# rpi_breakout.net
KiCad netlist of a schematic drawn in EAGLE
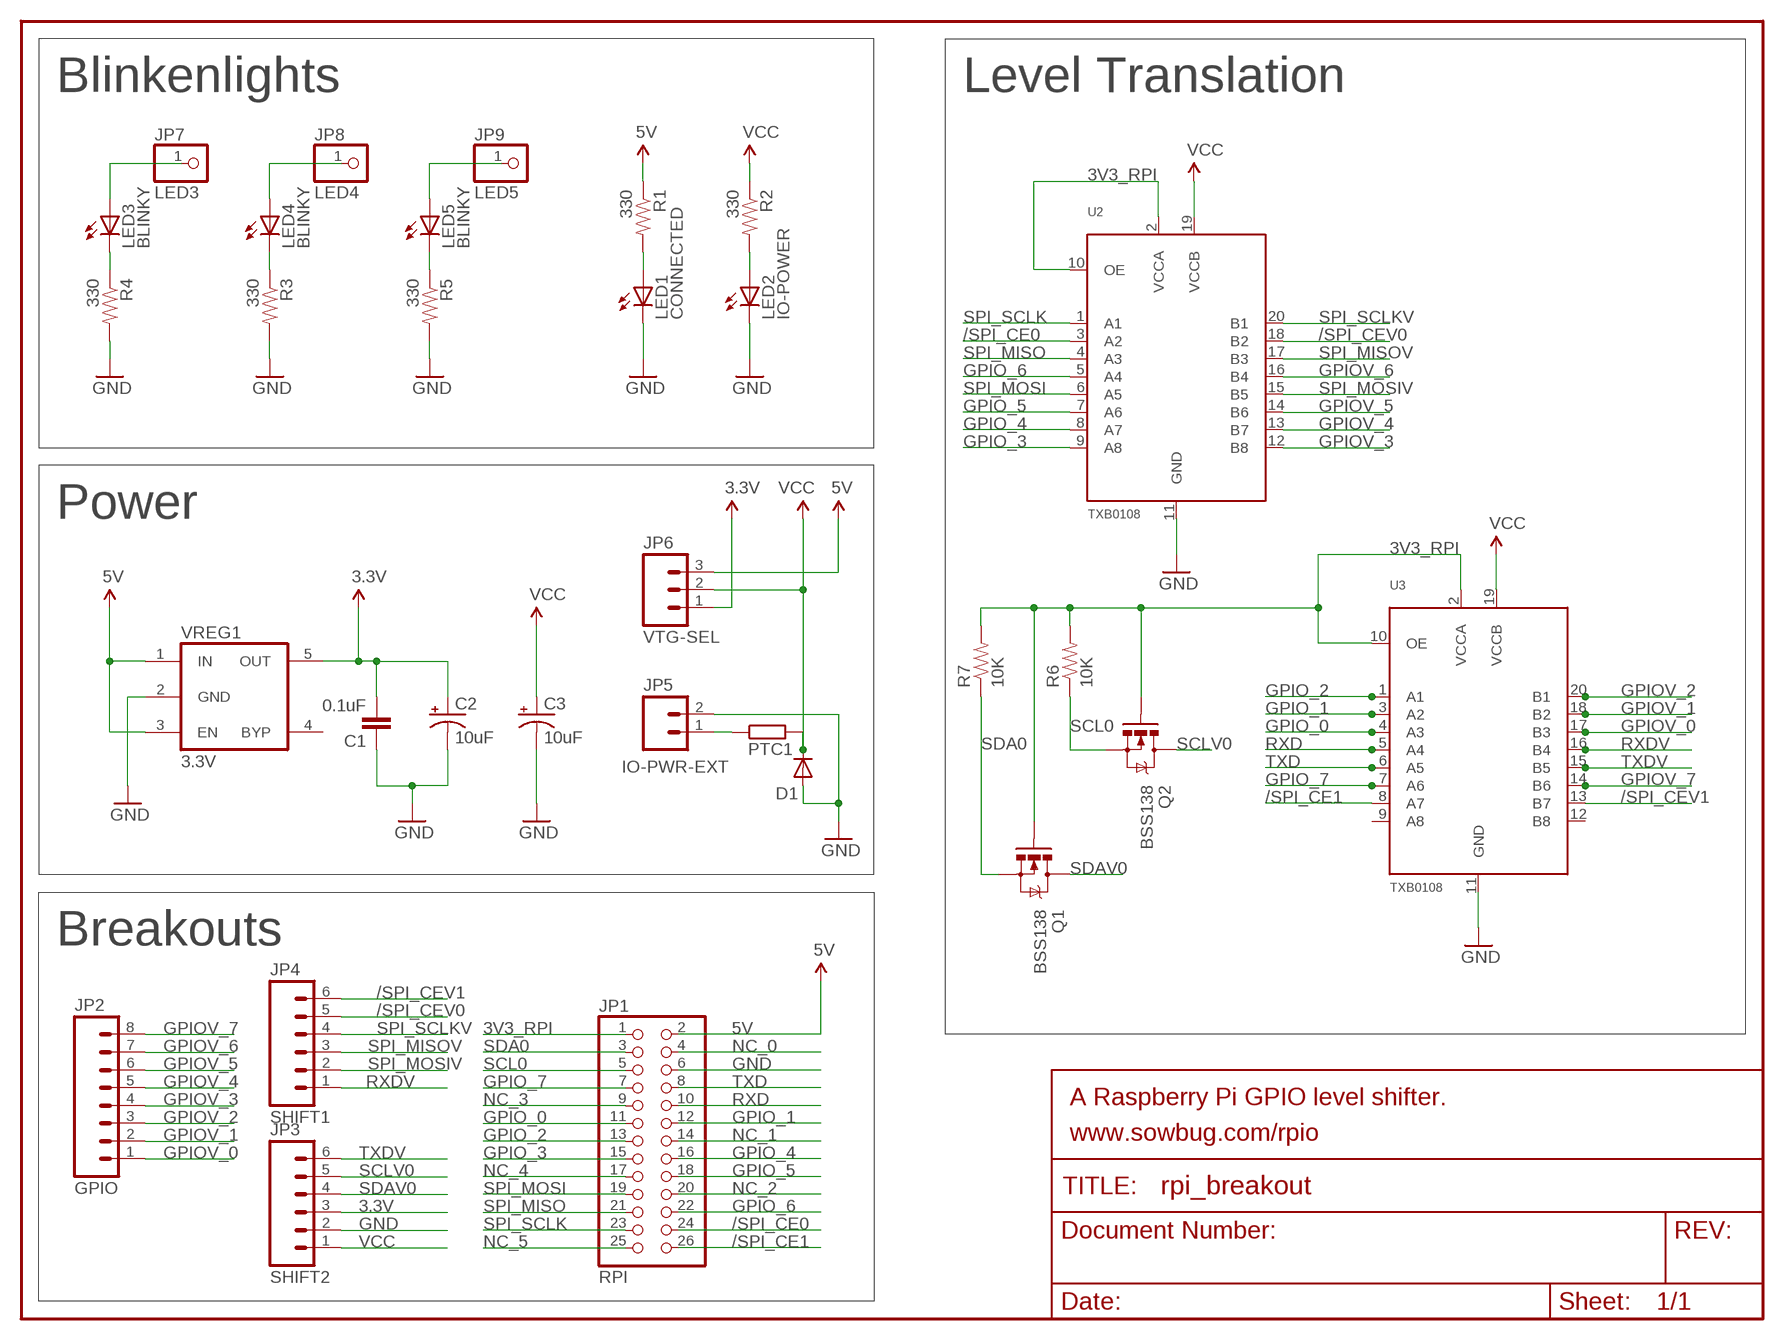
[diagram p0: schematic, sheet 1]

(export (version "E")
  (design (tool "Eeschema 10.0.6"))
  (components
    (comp (ref "C1")
      (value "0.1uF")
      (footprint "eagle-import:SPARKFUN_0805")
      (libsource (lib "eagle-import") (part "SPARKFUN_CAP0805"))
    )
    (comp (ref "C2")
      (value "10uF")
      (footprint "eagle-import:SPARKFUN_EIA3216")
      (libsource (lib "eagle-import") (part "SPARKFUN_CAP_POL1206"))
    )
    (comp (ref "C3")
      (value "10uF")
      (footprint "eagle-import:SPARKFUN_EIA3216")
      (libsource (lib "eagle-import") (part "SPARKFUN_CAP_POL1206"))
    )
    (comp (ref "D1")
      (value "SPARKFUN-DISCRETESEMI_DIODESOD")
      (footprint "eagle-import:SPARKFUN-DISCRETESEMI_SOD-323")
      (libsource (lib "eagle-import") (part "SPARKFUN-DISCRETESEMI_DIODESOD"))
    )
    (comp (ref "JP1")
      (value "RPI")
      (footprint "eagle-import:PINHEAD_2X13")
      (libsource (lib "eagle-import") (part "PINHEAD_PINHD-2X13"))
    )
    (comp (ref "JP2")
      (value "GPIO")
      (footprint "eagle-import:SPARKFUN_1X08_LOCK")
      (libsource (lib "eagle-import") (part "SPARKFUN_M08LOCK"))
    )
    (comp (ref "JP3")
      (value "SHIFT2")
      (footprint "eagle-import:SPARKFUN_1X06_LOCK")
      (libsource (lib "eagle-import") (part "SPARKFUN_M06LOCK"))
    )
    (comp (ref "JP4")
      (value "SHIFT1")
      (footprint "eagle-import:SPARKFUN_1X06_LOCK")
      (libsource (lib "eagle-import") (part "SPARKFUN_M06LOCK"))
    )
    (comp (ref "JP5")
      (value "IO-PWR-EXT")
      (footprint "eagle-import:SPARKFUN_1X02_LOCK")
      (libsource (lib "eagle-import") (part "SPARKFUN_M02LOCK"))
    )
    (comp (ref "JP6")
      (value "VTG-SEL")
      (footprint "eagle-import:SPARKFUN_1X03_LOCK")
      (libsource (lib "eagle-import") (part "SPARKFUN_M03LOCK"))
    )
    (comp (ref "JP7")
      (value "LED3")
      (footprint "eagle-import:ADAFRUIT_1X01")
      (libsource (lib "eagle-import") (part "ADAFRUIT_PINHD-1X1"))
    )
    (comp (ref "JP8")
      (value "LED4")
      (footprint "eagle-import:ADAFRUIT_1X01")
      (libsource (lib "eagle-import") (part "ADAFRUIT_PINHD-1X1"))
    )
    (comp (ref "JP9")
      (value "LED5")
      (footprint "eagle-import:ADAFRUIT_1X01")
      (libsource (lib "eagle-import") (part "ADAFRUIT_PINHD-1X1"))
    )
    (comp (ref "LED1")
      (value "CONNECTED")
      (footprint "eagle-import:PROGRAMMER_CHIP-LED0805")
      (libsource (lib "eagle-import") (part "PROGRAMMER_SPARKFUN_LED"))
    )
    (comp (ref "LED2")
      (value "IO-POWER")
      (footprint "eagle-import:PROGRAMMER_CHIP-LED0805")
      (libsource (lib "eagle-import") (part "PROGRAMMER_SPARKFUN_LED"))
    )
    (comp (ref "LED3")
      (value "BLINKY")
      (footprint "eagle-import:PROGRAMMER_CHIP-LED0805")
      (libsource (lib "eagle-import") (part "PROGRAMMER_SPARKFUN_LED"))
    )
    (comp (ref "LED4")
      (value "BLINKY")
      (footprint "eagle-import:PROGRAMMER_CHIP-LED0805")
      (libsource (lib "eagle-import") (part "PROGRAMMER_SPARKFUN_LED"))
    )
    (comp (ref "LED5")
      (value "BLINKY")
      (footprint "eagle-import:PROGRAMMER_CHIP-LED0805")
      (libsource (lib "eagle-import") (part "PROGRAMMER_SPARKFUN_LED"))
    )
    (comp (ref "PTC1")
      (value "RCL_R-EU_R1206")
      (footprint "eagle-import:RCL_R1206")
      (libsource (lib "eagle-import") (part "RCL_R-EU_R1206"))
    )
    (comp (ref "Q1")
      (value "BSS138")
      (footprint "eagle-import:SPARKFUN_SOT23-3")
      (libsource (lib "eagle-import") (part "SPARKFUN_MOSFET-NCHANNELSMD"))
    )
    (comp (ref "Q2")
      (value "BSS138")
      (footprint "eagle-import:SPARKFUN_SOT23-3")
      (libsource (lib "eagle-import") (part "SPARKFUN_MOSFET-NCHANNELSMD"))
    )
    (comp (ref "R1")
      (value "330")
      (footprint "eagle-import:SPARKFUN_0805")
      (libsource (lib "eagle-import") (part "SPARKFUN_RESISTOR0805-RES"))
    )
    (comp (ref "R2")
      (value "330")
      (footprint "eagle-import:SPARKFUN_0805")
      (libsource (lib "eagle-import") (part "SPARKFUN_RESISTOR0805-RES"))
    )
    (comp (ref "R3")
      (value "330")
      (footprint "eagle-import:SPARKFUN_0805")
      (libsource (lib "eagle-import") (part "SPARKFUN_RESISTOR0805-RES"))
    )
    (comp (ref "R4")
      (value "330")
      (footprint "eagle-import:SPARKFUN_0805")
      (libsource (lib "eagle-import") (part "SPARKFUN_RESISTOR0805-RES"))
    )
    (comp (ref "R5")
      (value "330")
      (footprint "eagle-import:SPARKFUN_0805")
      (libsource (lib "eagle-import") (part "SPARKFUN_RESISTOR0805-RES"))
    )
    (comp (ref "R6")
      (value "10K")
      (footprint "eagle-import:SPARKFUN_0805")
      (libsource (lib "eagle-import") (part "SPARKFUN_RESISTOR0805-RES"))
    )
    (comp (ref "R7")
      (value "10K")
      (footprint "eagle-import:SPARKFUN_0805")
      (libsource (lib "eagle-import") (part "SPARKFUN_RESISTOR0805-RES"))
    )
    (comp (ref "U2")
      (value "TXB0108")
      (footprint "eagle-import:RPI_BREAKOUT_TSSOP20")
      (libsource (lib "eagle-import") (part "RPI_BREAKOUT_TXB0108PWR"))
    )
    (comp (ref "U3")
      (value "TXB0108")
      (footprint "eagle-import:RPI_BREAKOUT_TSSOP20")
      (libsource (lib "eagle-import") (part "RPI_BREAKOUT_TXB0108PWR"))
    )
    (comp (ref "VREG1")
      (value "3.3V")
      (footprint "eagle-import:DP_DEVICES_SOT-23-5")
      (libsource (lib "eagle-import") (part "DP_DEVICES_IC_VREG_5PINS-SOT-23-5"))
    )
  )
  (nets
    (net (code "1") (name "/3V3_RPI") (class "Default")
      (node (ref "JP1") (pin "1") (pinfunction "1_1") (pintype "passive"))
      (node (ref "Q1") (pin "1") (pinfunction "G_1") (pintype "passive"))
      (node (ref "Q2") (pin "1") (pinfunction "G_1") (pintype "passive"))
      (node (ref "R6") (pin "2") (pinfunction "2_2") (pintype "passive"))
      (node (ref "R7") (pin "2") (pinfunction "2_2") (pintype "passive"))
      (node (ref "U2") (pin "10") (pinfunction "OE_10") (pintype "bidirectional"))
      (node (ref "U2") (pin "2") (pinfunction "VCCA_2") (pintype "bidirectional"))
      (node (ref "U3") (pin "10") (pinfunction "OE_10") (pintype "bidirectional"))
      (node (ref "U3") (pin "2") (pinfunction "VCCA_2") (pintype "bidirectional"))
    )
    (net (code "2") (name "/GPIOV_0") (class "Default")
      (node (ref "JP2") (pin "1") (pinfunction "1_1") (pintype "passive"))
      (node (ref "U3") (pin "17") (pinfunction "B3_17") (pintype "bidirectional"))
    )
    (net (code "3") (name "/GPIOV_1") (class "Default")
      (node (ref "JP2") (pin "2") (pinfunction "2_2") (pintype "passive"))
      (node (ref "U3") (pin "18") (pinfunction "B2_18") (pintype "bidirectional"))
    )
    (net (code "4") (name "/GPIOV_2") (class "Default")
      (node (ref "JP2") (pin "3") (pinfunction "3_3") (pintype "passive"))
      (node (ref "U3") (pin "20") (pinfunction "B1_20") (pintype "bidirectional"))
    )
    (net (code "5") (name "/GPIOV_3") (class "Default")
      (node (ref "JP2") (pin "4") (pinfunction "4_4") (pintype "passive"))
      (node (ref "U2") (pin "12") (pinfunction "B8_12") (pintype "bidirectional"))
    )
    (net (code "6") (name "/GPIOV_4") (class "Default")
      (node (ref "JP2") (pin "5") (pinfunction "5_5") (pintype "passive"))
      (node (ref "U2") (pin "13") (pinfunction "B7_13") (pintype "bidirectional"))
    )
    (net (code "7") (name "/GPIOV_5") (class "Default")
      (node (ref "JP2") (pin "6") (pinfunction "6_6") (pintype "passive"))
      (node (ref "U2") (pin "14") (pinfunction "B6_14") (pintype "bidirectional"))
    )
    (net (code "8") (name "/GPIOV_6") (class "Default")
      (node (ref "JP2") (pin "7") (pinfunction "7_7") (pintype "passive"))
      (node (ref "U2") (pin "16") (pinfunction "B4_16") (pintype "bidirectional"))
    )
    (net (code "9") (name "/GPIOV_7") (class "Default")
      (node (ref "JP2") (pin "8") (pinfunction "8_8") (pintype "passive"))
      (node (ref "U3") (pin "14") (pinfunction "B6_14") (pintype "bidirectional"))
    )
    (net (code "10") (name "/GPIO_0") (class "Default")
      (node (ref "JP1") (pin "11") (pinfunction "11_11") (pintype "passive"))
      (node (ref "U3") (pin "4") (pinfunction "A3_4") (pintype "bidirectional"))
    )
    (net (code "11") (name "/GPIO_1") (class "Default")
      (node (ref "JP1") (pin "12") (pinfunction "12_12") (pintype "passive"))
      (node (ref "U3") (pin "3") (pinfunction "A2_3") (pintype "bidirectional"))
    )
    (net (code "12") (name "/GPIO_2") (class "Default")
      (node (ref "JP1") (pin "13") (pinfunction "13_13") (pintype "passive"))
      (node (ref "U3") (pin "1") (pinfunction "A1_1") (pintype "bidirectional"))
    )
    (net (code "13") (name "/GPIO_3") (class "Default")
      (node (ref "JP1") (pin "15") (pinfunction "15_15") (pintype "passive"))
      (node (ref "U2") (pin "9") (pinfunction "A8_9") (pintype "bidirectional"))
    )
    (net (code "14") (name "/GPIO_4") (class "Default")
      (node (ref "JP1") (pin "16") (pinfunction "16_16") (pintype "passive"))
      (node (ref "U2") (pin "8") (pinfunction "A7_8") (pintype "bidirectional"))
    )
    (net (code "15") (name "/GPIO_5") (class "Default")
      (node (ref "JP1") (pin "18") (pinfunction "18_18") (pintype "passive"))
      (node (ref "U2") (pin "7") (pinfunction "A6_7") (pintype "bidirectional"))
    )
    (net (code "16") (name "/GPIO_6") (class "Default")
      (node (ref "JP1") (pin "22") (pinfunction "22_22") (pintype "passive"))
      (node (ref "U2") (pin "5") (pinfunction "A4_5") (pintype "bidirectional"))
    )
    (net (code "17") (name "/GPIO_7") (class "Default")
      (node (ref "JP1") (pin "7") (pinfunction "7_7") (pintype "passive"))
      (node (ref "U3") (pin "7") (pinfunction "A6_7") (pintype "bidirectional"))
    )
    (net (code "18") (name "/NC_0") (class "Default")
      (node (ref "JP1") (pin "4") (pinfunction "4_4") (pintype "passive"))
    )
    (net (code "19") (name "/NC_1") (class "Default")
      (node (ref "JP1") (pin "14") (pinfunction "14_14") (pintype "passive"))
    )
    (net (code "20") (name "/NC_2") (class "Default")
      (node (ref "JP1") (pin "20") (pinfunction "20_20") (pintype "passive"))
    )
    (net (code "21") (name "/NC_3") (class "Default")
      (node (ref "JP1") (pin "9") (pinfunction "9_9") (pintype "passive"))
    )
    (net (code "22") (name "/NC_4") (class "Default")
      (node (ref "JP1") (pin "17") (pinfunction "17_17") (pintype "passive"))
    )
    (net (code "23") (name "/NC_5") (class "Default")
      (node (ref "JP1") (pin "25") (pinfunction "25_25") (pintype "passive"))
    )
    (net (code "24") (name "/RXD") (class "Default")
      (node (ref "JP1") (pin "10") (pinfunction "10_10") (pintype "passive"))
      (node (ref "U3") (pin "5") (pinfunction "A4_5") (pintype "bidirectional"))
    )
    (net (code "25") (name "/RXDV") (class "Default")
      (node (ref "JP4") (pin "1") (pinfunction "1_1") (pintype "passive"))
      (node (ref "U3") (pin "16") (pinfunction "B4_16") (pintype "bidirectional"))
    )
    (net (code "26") (name "/SCL0") (class "Default")
      (node (ref "JP1") (pin "5") (pinfunction "5_5") (pintype "passive"))
      (node (ref "Q2") (pin "2") (pinfunction "S_2") (pintype "passive"))
      (node (ref "R6") (pin "1") (pinfunction "1_1") (pintype "passive"))
    )
    (net (code "27") (name "/SCLV0") (class "Default")
      (node (ref "JP3") (pin "5") (pinfunction "5_5") (pintype "passive"))
      (node (ref "Q2") (pin "3") (pinfunction "D_3") (pintype "passive"))
    )
    (net (code "28") (name "/SDA0") (class "Default")
      (node (ref "JP1") (pin "3") (pinfunction "3_3") (pintype "passive"))
      (node (ref "Q1") (pin "2") (pinfunction "S_2") (pintype "passive"))
      (node (ref "R7") (pin "1") (pinfunction "1_1") (pintype "passive"))
    )
    (net (code "29") (name "/SDAV0") (class "Default")
      (node (ref "JP3") (pin "4") (pinfunction "4_4") (pintype "passive"))
      (node (ref "Q1") (pin "3") (pinfunction "D_3") (pintype "passive"))
    )
    (net (code "30") (name "/SPI_MISO") (class "Default")
      (node (ref "JP1") (pin "21") (pinfunction "21_21") (pintype "passive"))
      (node (ref "U2") (pin "4") (pinfunction "A3_4") (pintype "bidirectional"))
    )
    (net (code "31") (name "/SPI_MISOV") (class "Default")
      (node (ref "JP4") (pin "3") (pinfunction "3_3") (pintype "passive"))
      (node (ref "U2") (pin "17") (pinfunction "B3_17") (pintype "bidirectional"))
    )
    (net (code "32") (name "/SPI_MOSI") (class "Default")
      (node (ref "JP1") (pin "19") (pinfunction "19_19") (pintype "passive"))
      (node (ref "U2") (pin "6") (pinfunction "A5_6") (pintype "bidirectional"))
    )
    (net (code "33") (name "/SPI_MOSIV") (class "Default")
      (node (ref "JP4") (pin "2") (pinfunction "2_2") (pintype "passive"))
      (node (ref "U2") (pin "15") (pinfunction "B5_15") (pintype "bidirectional"))
    )
    (net (code "34") (name "/SPI_SCLK") (class "Default")
      (node (ref "JP1") (pin "23") (pinfunction "23_23") (pintype "passive"))
      (node (ref "U2") (pin "1") (pinfunction "A1_1") (pintype "bidirectional"))
    )
    (net (code "35") (name "/SPI_SCLKV") (class "Default")
      (node (ref "JP4") (pin "4") (pinfunction "4_4") (pintype "passive"))
      (node (ref "U2") (pin "20") (pinfunction "B1_20") (pintype "bidirectional"))
    )
    (net (code "36") (name "/TXD") (class "Default")
      (node (ref "JP1") (pin "8") (pinfunction "8_8") (pintype "passive"))
      (node (ref "U3") (pin "6") (pinfunction "A5_6") (pintype "bidirectional"))
    )
    (net (code "37") (name "/TXDV") (class "Default")
      (node (ref "JP3") (pin "6") (pinfunction "6_6") (pintype "passive"))
      (node (ref "U3") (pin "15") (pinfunction "B5_15") (pintype "bidirectional"))
    )
    (net (code "38") (name "/{slash}SPI_CE0") (class "Default")
      (node (ref "JP1") (pin "24") (pinfunction "24_24") (pintype "passive"))
      (node (ref "U2") (pin "3") (pinfunction "A2_3") (pintype "bidirectional"))
    )
    (net (code "39") (name "/{slash}SPI_CE1") (class "Default")
      (node (ref "JP1") (pin "26") (pinfunction "26_26") (pintype "passive"))
      (node (ref "U3") (pin "8") (pinfunction "A7_8") (pintype "bidirectional"))
    )
    (net (code "40") (name "/{slash}SPI_CEV0") (class "Default")
      (node (ref "JP4") (pin "5") (pinfunction "5_5") (pintype "passive"))
      (node (ref "U2") (pin "18") (pinfunction "B2_18") (pintype "bidirectional"))
    )
    (net (code "41") (name "/{slash}SPI_CEV1") (class "Default")
      (node (ref "JP4") (pin "6") (pinfunction "6_6") (pintype "passive"))
      (node (ref "U3") (pin "13") (pinfunction "B7_13") (pintype "bidirectional"))
    )
    (net (code "42") (name "3.3V") (class "Default")
      (node (ref "C1") (pin "2") (pinfunction "2_2") (pintype "passive"))
      (node (ref "C2") (pin "A") (pinfunction "+_A") (pintype "passive"))
      (node (ref "JP3") (pin "3") (pinfunction "3_3") (pintype "passive"))
      (node (ref "JP6") (pin "1") (pinfunction "1_1") (pintype "passive"))
      (node (ref "VREG1") (pin "5") (pinfunction "OUT_5") (pintype "bidirectional"))
    )
    (net (code "43") (name "5V") (class "Default")
      (node (ref "JP1") (pin "2") (pinfunction "2_2") (pintype "passive"))
      (node (ref "JP6") (pin "3") (pinfunction "3_3") (pintype "passive"))
      (node (ref "R1") (pin "1") (pinfunction "1_1") (pintype "passive"))
      (node (ref "VREG1") (pin "1") (pinfunction "IN_1") (pintype "bidirectional"))
      (node (ref "VREG1") (pin "3") (pinfunction "EN_3") (pintype "bidirectional"))
    )
    (net (code "44") (name "GND") (class "Default")
      (node (ref "C1") (pin "1") (pinfunction "1_1") (pintype "passive"))
      (node (ref "C2") (pin "C") (pinfunction "-_C") (pintype "passive"))
      (node (ref "C3") (pin "C") (pinfunction "-_C") (pintype "passive"))
      (node (ref "D1") (pin "2") (pinfunction "A_2") (pintype "passive"))
      (node (ref "JP1") (pin "6") (pinfunction "6_6") (pintype "passive"))
      (node (ref "JP3") (pin "2") (pinfunction "2_2") (pintype "passive"))
      (node (ref "JP5") (pin "2") (pinfunction "2_2") (pintype "passive"))
      (node (ref "LED1") (pin "C") (pinfunction "C_C") (pintype "passive"))
      (node (ref "LED2") (pin "C") (pinfunction "C_C") (pintype "passive"))
      (node (ref "R3") (pin "2") (pinfunction "2_2") (pintype "passive"))
      (node (ref "R4") (pin "2") (pinfunction "2_2") (pintype "passive"))
      (node (ref "R5") (pin "2") (pinfunction "2_2") (pintype "passive"))
      (node (ref "U2") (pin "11") (pinfunction "GND_11") (pintype "bidirectional"))
      (node (ref "U3") (pin "11") (pinfunction "GND_11") (pintype "bidirectional"))
      (node (ref "VREG1") (pin "2") (pinfunction "GND_2") (pintype "bidirectional"))
    )
    (net (code "45") (name "Net-(JP5-Pad1)") (class "Default")
      (node (ref "JP5") (pin "1") (pinfunction "1_1") (pintype "passive"))
      (node (ref "PTC1") (pin "1") (pinfunction "1_1") (pintype "passive"))
    )
    (net (code "46") (name "Net-(JP7-Pad1)") (class "Default")
      (node (ref "JP7") (pin "1") (pinfunction "1_1") (pintype "passive"))
      (node (ref "LED3") (pin "A") (pinfunction "A_A") (pintype "passive"))
    )
    (net (code "47") (name "Net-(JP8-Pad1)") (class "Default")
      (node (ref "JP8") (pin "1") (pinfunction "1_1") (pintype "passive"))
      (node (ref "LED4") (pin "A") (pinfunction "A_A") (pintype "passive"))
    )
    (net (code "48") (name "Net-(JP9-Pad1)") (class "Default")
      (node (ref "JP9") (pin "1") (pinfunction "1_1") (pintype "passive"))
      (node (ref "LED5") (pin "A") (pinfunction "A_A") (pintype "passive"))
    )
    (net (code "49") (name "Net-(LED1-PadA)") (class "Default")
      (node (ref "LED1") (pin "A") (pinfunction "A_A") (pintype "passive"))
      (node (ref "R1") (pin "2") (pinfunction "2_2") (pintype "passive"))
    )
    (net (code "50") (name "Net-(LED2-PadA)") (class "Default")
      (node (ref "LED2") (pin "A") (pinfunction "A_A") (pintype "passive"))
      (node (ref "R2") (pin "2") (pinfunction "2_2") (pintype "passive"))
    )
    (net (code "51") (name "Net-(LED3-PadC)") (class "Default")
      (node (ref "LED3") (pin "C") (pinfunction "C_C") (pintype "passive"))
      (node (ref "R4") (pin "1") (pinfunction "1_1") (pintype "passive"))
    )
    (net (code "52") (name "Net-(LED4-PadC)") (class "Default")
      (node (ref "LED4") (pin "C") (pinfunction "C_C") (pintype "passive"))
      (node (ref "R3") (pin "1") (pinfunction "1_1") (pintype "passive"))
    )
    (net (code "53") (name "Net-(LED5-PadC)") (class "Default")
      (node (ref "LED5") (pin "C") (pinfunction "C_C") (pintype "passive"))
      (node (ref "R5") (pin "1") (pinfunction "1_1") (pintype "passive"))
    )
    (net (code "54") (name "VCC") (class "Default")
      (node (ref "C3") (pin "A") (pinfunction "+_A") (pintype "passive"))
      (node (ref "D1") (pin "1") (pinfunction "C_1") (pintype "passive"))
      (node (ref "JP3") (pin "1") (pinfunction "1_1") (pintype "passive"))
      (node (ref "JP6") (pin "2") (pinfunction "2_2") (pintype "passive"))
      (node (ref "PTC1") (pin "2") (pinfunction "2_2") (pintype "passive"))
      (node (ref "R2") (pin "1") (pinfunction "1_1") (pintype "passive"))
      (node (ref "U2") (pin "19") (pinfunction "VCCB_19") (pintype "bidirectional"))
      (node (ref "U3") (pin "19") (pinfunction "VCCB_19") (pintype "bidirectional"))
    )
    (net (code "55") (name "unconnected-(U3-A8-Pad9)") (class "Default")
      (node (ref "U3") (pin "9") (pinfunction "A8_9") (pintype "bidirectional"))
    )
    (net (code "56") (name "unconnected-(U3-B8-Pad12)") (class "Default")
      (node (ref "U3") (pin "12") (pinfunction "B8_12") (pintype "bidirectional"))
    )
    (net (code "57") (name "unconnected-(VREG1-BYP-Pad4)") (class "Default")
      (node (ref "VREG1") (pin "4") (pinfunction "BYP_4") (pintype "bidirectional"))
    )
  )
)
